# Power.net
KiCad netlist of a schematic drawn in Altium Designer
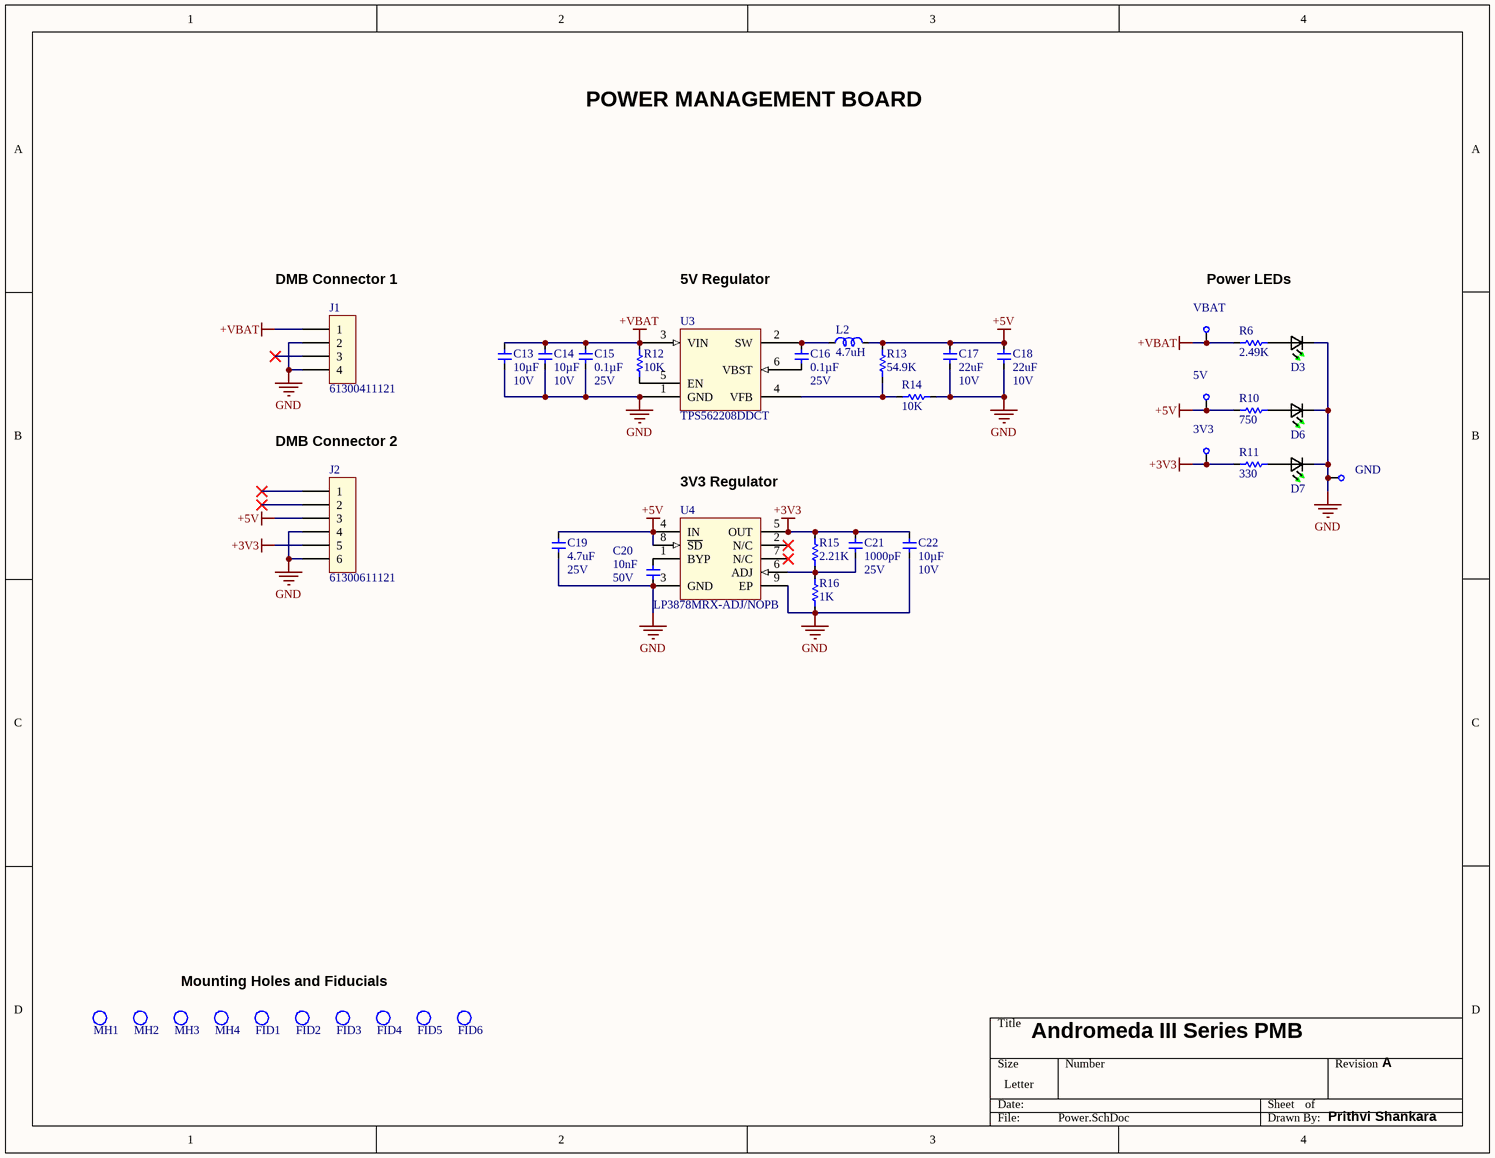
[diagram p0: Power.SchDoc]

(export (version "E")
  (design (tool "Eeschema 10.0.6"))
  (components
    (comp (ref "3V3")
      (value "Testpoint")
      (footprint "Testpoint")
      (description "TESTPOINT 0.7MMD Hole, 1.2MMW, 1.2MML")
      (libsource (lib "SOARSchematics") (part "Testpoint"))
    )
    (comp (ref "5V")
      (value "Testpoint")
      (footprint "Testpoint")
      (description "TESTPOINT 0.7MMD Hole, 1.2MMW, 1.2MML")
      (libsource (lib "SOARSchematics") (part "Testpoint"))
    )
    (comp (ref "C13")
      (value "CL10A106MP8NNNC")
      (footprint "0603[1608]")
      (description "CAP CER 10UF 10V X5R 0603")
      (fields
        (field (name "MANUFACTURER") "Samsung Electro-Mechanics")
        (field (name "TOLERANCE") "±20%")
        (field (name "CAPACITANCE") "10µF")
        (field (name "VOLTAGE - RATED") "10V")
      )
      (libsource (lib "SOARSchematics") (part "CL10A106MP8NNNC"))
    )
    (comp (ref "C14")
      (value "CL10A106MP8NNNC")
      (footprint "0603[1608]")
      (description "CAP CER 10UF 10V X5R 0603")
      (fields
        (field (name "MANUFACTURER") "Samsung Electro-Mechanics")
        (field (name "TOLERANCE") "±20%")
        (field (name "CAPACITANCE") "10µF")
        (field (name "VOLTAGE - RATED") "10V")
      )
      (libsource (lib "SOARSchematics") (part "CL10A106MP8NNNC"))
    )
    (comp (ref "C15")
      (value "CGA3E2X7R1E104K080AA")
      (footprint "0603[1608]")
      (description "CAP CER 0.1UF 25V X7R 0603")
      (fields
        (field (name "MANUFACTURER") "TDK Corporation")
        (field (name "TOLERANCE") "±10%")
        (field (name "CAPACITANCE") "0.1µF")
        (field (name "VOLTAGE - RATED") "25V")
      )
      (libsource (lib "SOARSchematics") (part "CGA3E2X7R1E104K080AA"))
    )
    (comp (ref "C16")
      (value "CGA3E2X7R1E104K080AA")
      (footprint "0603[1608]")
      (description "CAP CER 0.1UF 25V X7R 0603")
      (fields
        (field (name "MANUFACTURER") "TDK Corporation")
        (field (name "TOLERANCE") "±10%")
        (field (name "CAPACITANCE") "0.1µF")
        (field (name "VOLTAGE - RATED") "25V")
      )
      (libsource (lib "SOARSchematics") (part "CGA3E2X7R1E104K080AA"))
    )
    (comp (ref "C17")
      (value "C1608X5R1A226M080AC")
      (footprint "0603[1608]")
      (description "CAP CER 22UF 10V X5R 0603")
      (fields
        (field (name "MANUFACTURER") "TDK Corporation")
        (field (name "TOLERANCE") "±20%")
        (field (name "CAPACITANCE") "22uF")
        (field (name "VOLTAGE - RATED") "10V")
      )
      (libsource (lib "SOARSchematics") (part "C1608X5R1A226M080AC"))
    )
    (comp (ref "C18")
      (value "C1608X5R1A226M080AC")
      (footprint "0603[1608]")
      (description "CAP CER 22UF 10V X5R 0603")
      (fields
        (field (name "MANUFACTURER") "TDK Corporation")
        (field (name "TOLERANCE") "±20%")
        (field (name "CAPACITANCE") "22uF")
        (field (name "VOLTAGE - RATED") "10V")
      )
      (libsource (lib "SOARSchematics") (part "C1608X5R1A226M080AC"))
    )
    (comp (ref "C19")
      (value "CL10A475KA8NQNC")
      (footprint "0603[1608]")
      (description "CAP CER 4.7UF 25V X5R 0603")
      (fields
        (field (name "MANUFACTURER") "Samsung Electro-Mechanics")
        (field (name "TOLERANCE") "±10%")
        (field (name "CAPACITANCE") "4.7uF")
        (field (name "VOLTAGE - RATED") "25V")
      )
      (libsource (lib "SOARSchematics") (part "CL10A475KA8NQNC"))
    )
    (comp (ref "C20")
      (value "GRM1885C1H103JA01D")
      (footprint "0603[1608]")
      (description "CAP CER 10000PF 50V C0G/NP0 0603")
      (fields
        (field (name "MANUFACTURER") "Murata Electronics")
        (field (name "TOLERANCE") "±50%")
        (field (name "CAPACITANCE") "10nF")
        (field (name "VOLTAGE - RATED") "50V")
      )
      (libsource (lib "SOARSchematics") (part "GRM1885C1H103JA01D"))
    )
    (comp (ref "C21")
      (value "C0603C102K3GACTU")
      (footprint "0603[1608]")
      (description "CAP CER 1000PF 25V C0G/NP0 0603")
      (fields
        (field (name "MANUFACTURER") "KEMET")
        (field (name "TOLERANCE") "±10%")
        (field (name "CAPACITANCE") "1000pF")
        (field (name "VOLTAGE - RATED") "25V")
      )
      (libsource (lib "SOARSchematics") (part "C0603C102K3GACTU"))
    )
    (comp (ref "C22")
      (value "CL10A106MP8NNNC")
      (footprint "0603[1608]")
      (description "CAP CER 10UF 10V X5R 0603")
      (fields
        (field (name "MANUFACTURER") "Samsung Electro-Mechanics")
        (field (name "TOLERANCE") "±20%")
        (field (name "CAPACITANCE") "10µF")
        (field (name "VOLTAGE - RATED") "10V")
      )
      (libsource (lib "SOARSchematics") (part "CL10A106MP8NNNC"))
    )
    (comp (ref "D3")
      (value "LTST-C191KGKT")
      (footprint "LTST-C191KGKT")
      (description "LED GREEN CLEAR SMD 0603")
      (fields (field (name "MANUFACTURER") "Lite-On Inc."))
      (libsource (lib "SOARSchematics") (part "LTST-C191KGKT"))
    )
    (comp (ref "D6")
      (value "LTST-C191KGKT")
      (footprint "LTST-C191KGKT")
      (description "LED GREEN CLEAR SMD 0603")
      (fields (field (name "MANUFACTURER") "Lite-On Inc."))
      (libsource (lib "SOARSchematics") (part "LTST-C191KGKT"))
    )
    (comp (ref "D7")
      (value "LTST-C191KGKT")
      (footprint "LTST-C191KGKT")
      (description "LED GREEN CLEAR SMD 0603")
      (fields (field (name "MANUFACTURER") "Lite-On Inc."))
      (libsource (lib "SOARSchematics") (part "LTST-C191KGKT"))
    )
    (comp (ref "FID1")
      (value "FID_1MM_ROUND_SL")
      (footprint "FID_1MM_ROUND_SL")
      (description "Fiducial 1mm Round Single Layer")
      (libsource (lib "SOARSchematics") (part "FID_1MM_ROUND_SL"))
    )
    (comp (ref "FID2")
      (value "FID_1MM_ROUND_SL")
      (footprint "FID_1MM_ROUND_SL")
      (description "Fiducial 1mm Round Single Layer")
      (libsource (lib "SOARSchematics") (part "FID_1MM_ROUND_SL"))
    )
    (comp (ref "FID3")
      (value "FID_1MM_ROUND_SL")
      (footprint "FID_1MM_ROUND_SL")
      (description "Fiducial 1mm Round Single Layer")
      (libsource (lib "SOARSchematics") (part "FID_1MM_ROUND_SL"))
    )
    (comp (ref "FID4")
      (value "FID_1MM_ROUND_SL")
      (footprint "FID_1MM_ROUND_SL")
      (description "Fiducial 1mm Round Single Layer")
      (libsource (lib "SOARSchematics") (part "FID_1MM_ROUND_SL"))
    )
    (comp (ref "FID5")
      (value "FID_1MM_ROUND_SL")
      (footprint "FID_1MM_ROUND_SL")
      (description "Fiducial 1mm Round Single Layer")
      (libsource (lib "SOARSchematics") (part "FID_1MM_ROUND_SL"))
    )
    (comp (ref "FID6")
      (value "FID_1MM_ROUND_SL")
      (footprint "FID_1MM_ROUND_SL")
      (description "Fiducial 1mm Round Single Layer")
      (libsource (lib "SOARSchematics") (part "FID_1MM_ROUND_SL"))
    )
    (comp (ref "GND")
      (value "Testpoint")
      (footprint "Testpoint")
      (description "TESTPOINT 0.7MMD Hole, 1.2MMW, 1.2MML")
      (libsource (lib "SOARSchematics") (part "Testpoint"))
    )
    (comp (ref "J1")
      (value "61300411121")
      (footprint "61300411121")
      (description "CONN HEADER VERT 4POS MALE 2.54MM")
      (fields (field (name "MANUFACTURER") "Würth Elektronik"))
      (libsource (lib "SOARSchematics") (part "61300411121"))
    )
    (comp (ref "J2")
      (value "61300611121")
      (footprint "61300611121")
      (description "CONN HEADER VERT 6POS MALE 2.54MM")
      (fields (field (name "MANUFACTURER") "Würth Elektronik"))
      (libsource (lib "SOARSchematics") (part "61300611121"))
    )
    (comp (ref "L2")
      (value "4.7uH")
      (footprint "DFE252012P-4R7M=P2")
      (description "FIXED IND 4.7UH 2A 200 MOHM SMD")
      (fields (field (name "MANUFACTURER") "Murata Electronics") (field (name "TOLERANCE") "+-20%"))
      (libsource (lib "SOARSchematics") (part "DFE252012P-4R7M=P2"))
    )
    (comp (ref "MH1")
      (value "9774110360R")
      (footprint "Standoff")
      (description "ROUND STANDOFF M3X0.5 STEEL 11MM")
      (fields (field (name "MANUFACTURER") "Würth Elektronik"))
      (libsource (lib "SOARSchematics") (part "9774110360R"))
    )
    (comp (ref "MH2")
      (value "9774110360R")
      (footprint "Standoff")
      (description "ROUND STANDOFF M3X0.5 STEEL 11MM")
      (fields (field (name "MANUFACTURER") "Würth Elektronik"))
      (libsource (lib "SOARSchematics") (part "9774110360R"))
    )
    (comp (ref "MH3")
      (value "Mounting Hole")
      (footprint "MOUNT-HOLE")
      (description "#4 Screw, 0.116in Diameter")
      (libsource (lib "SOARSchematics") (part "Mounting Hole"))
    )
    (comp (ref "MH4")
      (value "Mounting Hole")
      (footprint "MOUNT-HOLE")
      (description "#4 Screw, 0.116in Diameter")
      (libsource (lib "SOARSchematics") (part "Mounting Hole"))
    )
    (comp (ref "R6")
      (value "ERA-3AEB2491V")
      (footprint "0603[1608]")
      (description "RES SMD 2.49KOHM 0.1% 1/10W 0603")
      (fields
        (field (name "TOLERANCE") "±0.1%")
        (field (name "MANUFACTURER") "Panasonic Electronic Components")
        (field (name "RESISTANCE") "2.49K")
      )
      (libsource (lib "SOARSchematics") (part "ERA-3AEB2491V"))
    )
    (comp (ref "R10")
      (value "ESR03EZPJ751")
      (footprint "0603[1608]")
      (description "RES SMD 750 OHM 5% 1/4W 0603")
      (fields
        (field (name "TOLERANCE") "±5%")
        (field (name "MANUFACTURER") "Rohm Semiconductor")
        (field (name "RESISTANCE") "750")
      )
      (libsource (lib "SOARSchematics") (part "ESR03EZPJ751"))
    )
    (comp (ref "R11")
      (value "RC1608F331CS")
      (footprint "0603[1608]")
      (description "RES SMD 330 OHM 1% 1/10W 0603")
      (fields
        (field (name "TOLERANCE") "±1%")
        (field (name "MANUFACTURER") "Samsung Electro-Mechanics")
        (field (name "RESISTANCE") "330")
      )
      (libsource (lib "SOARSchematics") (part "RC1608F331CS"))
    )
    (comp (ref "R12")
      (value "ERJ-3GEYJ103V")
      (footprint "0603[1608]")
      (description "RES SMD 10K OHM 5% 1/10W 0603")
      (fields
        (field (name "TOLERANCE") "±5%")
        (field (name "MANUFACTURER") "Panasonic Electronic Components")
        (field (name "RESISTANCE") "10K")
      )
      (libsource (lib "SOARSchematics") (part "ERJ-3GEYJ103V"))
    )
    (comp (ref "R13")
      (value "RC0603FR-0754K9L")
      (footprint "0603[1608]")
      (description "RES SMD 54.9K OHM 1% 1/10W 0603")
      (fields
        (field (name "TOLERANCE") "±1%")
        (field (name "MANUFACTURER") "Yageo")
        (field (name "RESISTANCE") "54.9K")
      )
      (libsource (lib "SOARSchematics") (part "RC0603FR-0754K9L"))
    )
    (comp (ref "R14")
      (value "ERJ-3GEYJ103V")
      (footprint "0603[1608]")
      (description "RES SMD 10K OHM 5% 1/10W 0603")
      (fields
        (field (name "TOLERANCE") "±5%")
        (field (name "MANUFACTURER") "Panasonic Electronic Components")
        (field (name "RESISTANCE") "10K")
      )
      (libsource (lib "SOARSchematics") (part "ERJ-3GEYJ103V"))
    )
    (comp (ref "R15")
      (value "ERJ-3EKF2211V")
      (footprint "0603[1608]")
      (description "RES SMD 2.21K OHM 1% 1/10W 0603")
      (fields
        (field (name "TOLERANCE") "±1%")
        (field (name "MANUFACTURER") "Panasonic Electronic Components")
        (field (name "RESISTANCE") "2.21K")
      )
      (libsource (lib "SOARSchematics") (part "ERJ-3EKF2211V"))
    )
    (comp (ref "R16")
      (value "RC0603FR-071KL")
      (footprint "0603[1608]")
      (description "RES SMD 1K OHM 1% 1/10W 0603")
      (fields
        (field (name "TOLERANCE") "±1%")
        (field (name "MANUFACTURER") "Yageo")
        (field (name "RESISTANCE") "1K")
      )
      (libsource (lib "SOARSchematics") (part "RC0603FR-071KL"))
    )
    (comp (ref "U3")
      (value "TPS562208DDCT")
      (footprint "TPS562208DDCT")
      (description "IC REG BUCK ADJ 2A TSOT23-6")
      (fields (field (name "MANUFACTURER") "Texas Instruments"))
      (libsource (lib "SOARSchematics") (part "TPS562208DDCT"))
    )
    (comp (ref "U4")
      (value "LP3878MRX-ADJ/NOPB")
      (footprint "SOIC127P600X170_HS-9N")
      (description "IC REG LIN POS ADJ 800MA 8SO")
      (fields (field (name "MANUFACTURER") "Texas Instruments") (field (name "BASE PART NUMBER") "LP3878"))
      (libsource (lib "SOARSchematics") (part "LP3878MRX-ADJ/NOPB"))
    )
    (comp (ref "VBAT")
      (value "Testpoint")
      (footprint "Testpoint")
      (description "TESTPOINT 0.7MMD Hole, 1.2MMW, 1.2MML")
      (libsource (lib "SOARSchematics") (part "Testpoint"))
    )
  )
  (nets
    (net (code "1") (name "+3V3") (class "Default")
      (node (ref "3V3") (pin "1") (pinfunction "1_1") (pintype "power_in"))
      (node (ref "C21") (pin "2") (pinfunction "2_2") (pintype "passive"))
      (node (ref "C22") (pin "2") (pinfunction "2_2") (pintype "passive"))
      (node (ref "J2") (pin "5") (pinfunction "5_5") (pintype "passive"))
      (node (ref "R11") (pin "1") (pinfunction "1_1") (pintype "passive"))
      (node (ref "R15") (pin "2") (pinfunction "2_2") (pintype "passive"))
      (node (ref "U4") (pin "5") (pinfunction "OUT_5") (pintype "power_in"))
    )
    (net (code "2") (name "+5V") (class "Default")
      (node (ref "5V") (pin "1") (pinfunction "1_1") (pintype "power_in"))
      (node (ref "C17") (pin "2") (pinfunction "2_2") (pintype "passive"))
      (node (ref "C18") (pin "2") (pinfunction "2_2") (pintype "passive"))
      (node (ref "C19") (pin "2") (pinfunction "2_2") (pintype "passive"))
      (node (ref "J2") (pin "3") (pinfunction "3_3") (pintype "passive"))
      (node (ref "L2") (pin "2") (pinfunction "2_2") (pintype "passive"))
      (node (ref "R10") (pin "1") (pinfunction "1_1") (pintype "passive"))
      (node (ref "R13") (pin "1") (pinfunction "1_1") (pintype "passive"))
      (node (ref "U4") (pin "4") (pinfunction "IN_4") (pintype "power_in"))
      (node (ref "U4") (pin "8") (pinfunction "~{SD}_8") (pintype "input"))
    )
    (net (code "3") (name "+VBAT") (class "Default")
      (node (ref "C13") (pin "2") (pinfunction "2_2") (pintype "passive"))
      (node (ref "C14") (pin "2") (pinfunction "2_2") (pintype "passive"))
      (node (ref "C15") (pin "2") (pinfunction "2_2") (pintype "passive"))
      (node (ref "J1") (pin "1") (pinfunction "1_1") (pintype "passive"))
      (node (ref "R12") (pin "2") (pinfunction "2_2") (pintype "passive"))
      (node (ref "R6") (pin "1") (pinfunction "1_1") (pintype "passive"))
      (node (ref "U3") (pin "3") (pinfunction "VIN_3") (pintype "input"))
      (node (ref "VBAT") (pin "1") (pinfunction "1_1") (pintype "power_in"))
    )
    (net (code "4") (name "GND") (class "Default")
      (node (ref "C13") (pin "1") (pinfunction "1_1") (pintype "passive"))
      (node (ref "C14") (pin "1") (pinfunction "1_1") (pintype "passive"))
      (node (ref "C15") (pin "1") (pinfunction "1_1") (pintype "passive"))
      (node (ref "C17") (pin "1") (pinfunction "1_1") (pintype "passive"))
      (node (ref "C18") (pin "1") (pinfunction "1_1") (pintype "passive"))
      (node (ref "C19") (pin "1") (pinfunction "1_1") (pintype "passive"))
      (node (ref "C20") (pin "1") (pinfunction "1_1") (pintype "passive"))
      (node (ref "C22") (pin "1") (pinfunction "1_1") (pintype "passive"))
      (node (ref "D3") (pin "1") (pinfunction "K2_1") (pintype "passive"))
      (node (ref "D6") (pin "1") (pinfunction "K2_1") (pintype "passive"))
      (node (ref "D7") (pin "1") (pinfunction "K2_1") (pintype "passive"))
      (node (ref "GND") (pin "1") (pinfunction "1_1") (pintype "power_in"))
      (node (ref "J1") (pin "2") (pinfunction "2_2") (pintype "passive"))
      (node (ref "J1") (pin "4") (pinfunction "4_4") (pintype "passive"))
      (node (ref "J2") (pin "4") (pinfunction "4_4") (pintype "passive"))
      (node (ref "J2") (pin "6") (pinfunction "6_6") (pintype "passive"))
      (node (ref "R14") (pin "1") (pinfunction "1_1") (pintype "passive"))
      (node (ref "R16") (pin "1") (pinfunction "1_1") (pintype "passive"))
      (node (ref "U3") (pin "1") (pinfunction "GND_1") (pintype "passive"))
      (node (ref "U4") (pin "3") (pinfunction "GND_3") (pintype "power_in"))
      (node (ref "U4") (pin "9") (pinfunction "EP_9") (pintype "power_in"))
    )
    (net (code "5") (name "Net-(D3-A2)") (class "Default")
      (node (ref "D3") (pin "2") (pinfunction "A2_2") (pintype "passive"))
      (node (ref "R6") (pin "2") (pinfunction "2_2") (pintype "passive"))
    )
    (net (code "6") (name "Net-(D6-A2)") (class "Default")
      (node (ref "D6") (pin "2") (pinfunction "A2_2") (pintype "passive"))
      (node (ref "R10") (pin "2") (pinfunction "2_2") (pintype "passive"))
    )
    (net (code "7") (name "Net-(D7-A2)") (class "Default")
      (node (ref "D7") (pin "2") (pinfunction "A2_2") (pintype "passive"))
      (node (ref "R11") (pin "2") (pinfunction "2_2") (pintype "passive"))
    )
    (net (code "8") (name "Net-(U3-EN)") (class "Default")
      (node (ref "R12") (pin "1") (pinfunction "1_1") (pintype "passive"))
      (node (ref "U3") (pin "5") (pinfunction "EN_5") (pintype "passive"))
    )
    (net (code "9") (name "Net-(U3-SW)") (class "Default")
      (node (ref "C16") (pin "2") (pinfunction "2_2") (pintype "passive"))
      (node (ref "L2") (pin "1") (pinfunction "1_1") (pintype "passive"))
      (node (ref "U3") (pin "2") (pinfunction "SW_2") (pintype "passive"))
    )
    (net (code "10") (name "Net-(U3-VBST)") (class "Default")
      (node (ref "C16") (pin "1") (pinfunction "1_1") (pintype "passive"))
      (node (ref "U3") (pin "6") (pinfunction "VBST_6") (pintype "input"))
    )
    (net (code "11") (name "Net-(U3-VFB)") (class "Default")
      (node (ref "R13") (pin "2") (pinfunction "2_2") (pintype "passive"))
      (node (ref "R14") (pin "2") (pinfunction "2_2") (pintype "passive"))
      (node (ref "U3") (pin "4") (pinfunction "VFB_4") (pintype "passive"))
    )
    (net (code "12") (name "Net-(U4-ADJ)") (class "Default")
      (node (ref "C21") (pin "1") (pinfunction "1_1") (pintype "passive"))
      (node (ref "R15") (pin "1") (pinfunction "1_1") (pintype "passive"))
      (node (ref "R16") (pin "2") (pinfunction "2_2") (pintype "passive"))
      (node (ref "U4") (pin "6") (pinfunction "ADJ_6") (pintype "input"))
    )
    (net (code "13") (name "Net-(U4-BYP)") (class "Default")
      (node (ref "C20") (pin "2") (pinfunction "2_2") (pintype "passive"))
      (node (ref "U4") (pin "1") (pinfunction "BYP_1") (pintype "passive"))
    )
    (net (code "14") (name "unconnected-(J1-Pad3)") (class "Default")
      (node (ref "J1") (pin "3") (pinfunction "3_3") (pintype "passive+no_connect"))
    )
    (net (code "15") (name "unconnected-(J2-Pad1)") (class "Default")
      (node (ref "J2") (pin "1") (pinfunction "1_1") (pintype "passive+no_connect"))
    )
    (net (code "16") (name "unconnected-(J2-Pad2)") (class "Default")
      (node (ref "J2") (pin "2") (pinfunction "2_2") (pintype "passive+no_connect"))
    )
    (net (code "17") (name "unconnected-(U4-N{slash}C-Pad2)") (class "Default")
      (node (ref "U4") (pin "2") (pinfunction "N/C_2") (pintype "passive+no_connect"))
    )
    (net (code "18") (name "unconnected-(U4-N{slash}C-Pad7)") (class "Default")
      (node (ref "U4") (pin "7") (pinfunction "N/C_7") (pintype "passive+no_connect"))
    )
  )
)
